# hh.net
KiCad netlist of a schematic drawn in EAGLE
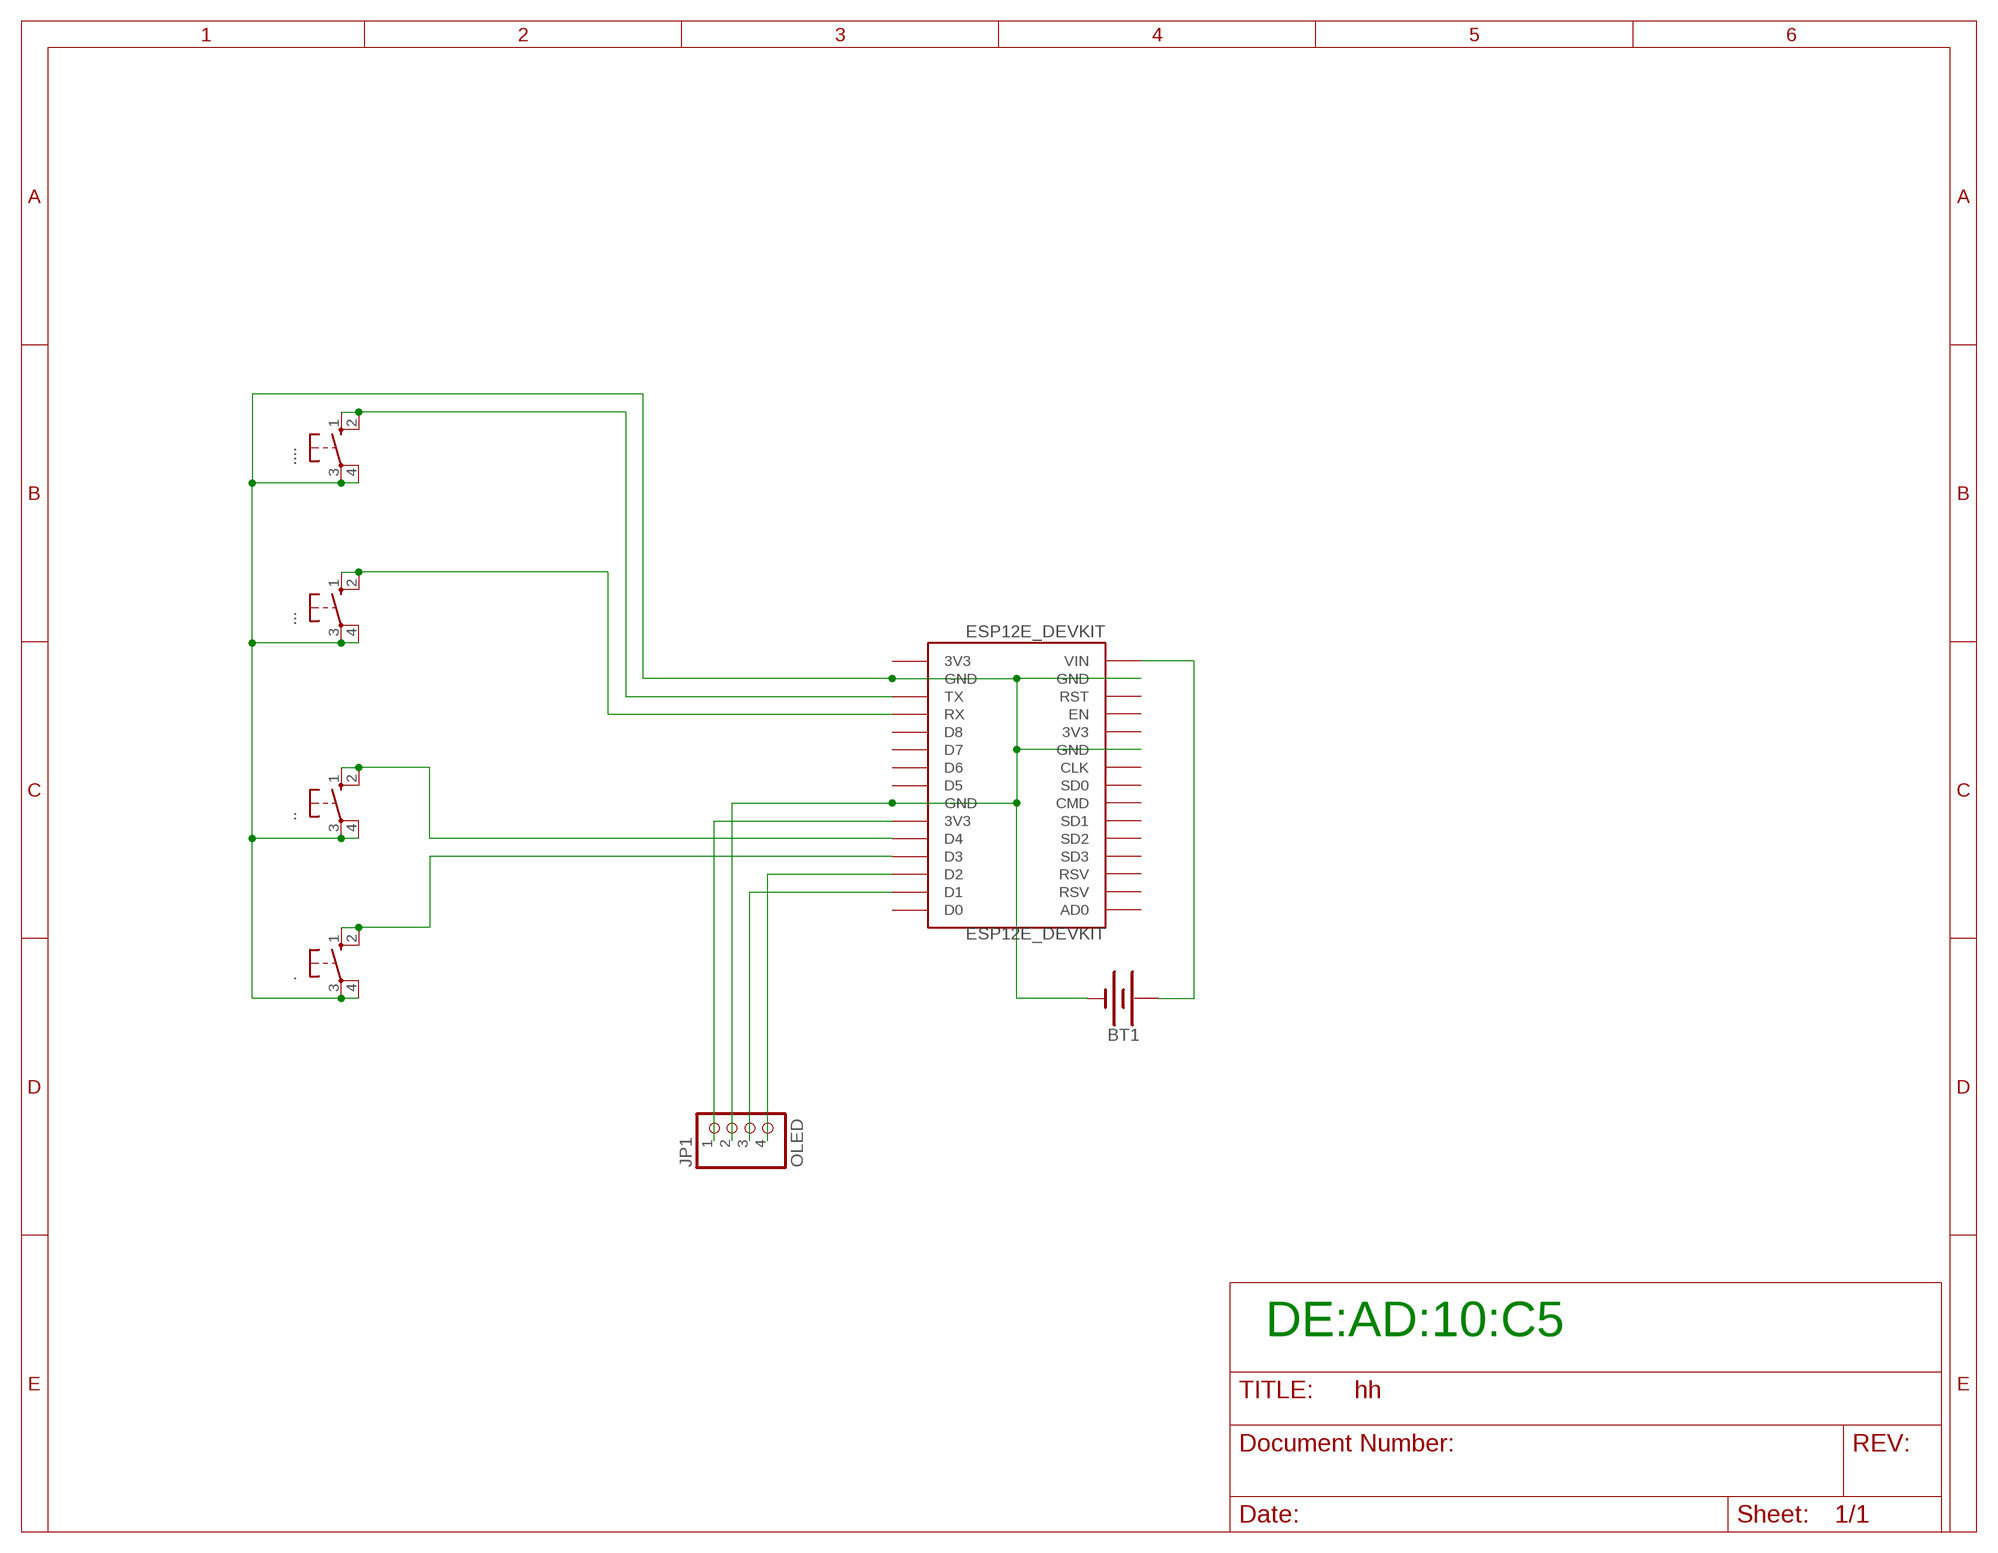
[diagram p0: schematic, sheet 1]

(export (version "E")
  (design (tool "Eeschema 10.0.6"))
  (components
    (comp (ref ".")
      (value "10-XX")
      (footprint "eagle-import:B3F-10XX")
      (fields (field (name "MPN") "B3F-1000"))
      (libsource (lib "eagle-import") (part "10-XX"))
    )
    (comp (ref "..")
      (value "10-XX")
      (footprint "eagle-import:B3F-10XX")
      (fields (field (name "MPN") "B3F-1000"))
      (libsource (lib "eagle-import") (part "10-XX"))
    )
    (comp (ref "...")
      (value "10-XX")
      (footprint "eagle-import:B3F-10XX")
      (fields (field (name "MPN") "B3F-1000"))
      (libsource (lib "eagle-import") (part "10-XX"))
    )
    (comp (ref "....")
      (value "10-XX")
      (footprint "eagle-import:B3F-10XX")
      (fields (field (name "MPN") "B3F-1000"))
      (libsource (lib "eagle-import") (part "10-XX"))
    )
    (comp (ref "BT1")
      (value "BATTERY-18650")
      (footprint "eagle-import:BATTERY_18650-HOLDER")
      (libsource (lib "eagle-import") (part "BATTERY-18650"))
    )
    (comp (ref "ESP12E_DEVKIT")
      (value "ESP12E_DEVKIT")
      (footprint "eagle-import:ESP12E_DEVKIT")
      (libsource (lib "eagle-import") (part "ESP12E_DEVKIT"))
    )
    (comp (ref "JP1")
      (value "OLED")
      (footprint "eagle-import:1X04")
      (libsource (lib "eagle-import") (part "PINHD-1X4"))
    )
  )
  (nets
    (net (code "1") (name "Net-(.-P)") (class "Default")
      (node (ref ".") (pin "3") (pinfunction "P_3") (pintype "passive"))
      (node (ref ".") (pin "4") (pinfunction "P1_4") (pintype "passive"))
      (node (ref "..") (pin "3") (pinfunction "P_3") (pintype "passive"))
      (node (ref "..") (pin "4") (pinfunction "P1_4") (pintype "passive"))
      (node (ref "...") (pin "3") (pinfunction "P_3") (pintype "passive"))
      (node (ref "...") (pin "4") (pinfunction "P1_4") (pintype "passive"))
      (node (ref "....") (pin "3") (pinfunction "P_3") (pintype "passive"))
      (node (ref "....") (pin "4") (pinfunction "P1_4") (pintype "passive"))
      (node (ref "BT1") (pin "GND@1") (pinfunction "-_GND@1") (pintype "power_in"))
      (node (ref "ESP12E_DEVKIT") (pin "GND@0") (pinfunction "GND_GND@0") (pintype "bidirectional"))
      (node (ref "ESP12E_DEVKIT") (pin "GND@1") (pinfunction "GND_GND@1") (pintype "bidirectional"))
      (node (ref "ESP12E_DEVKIT") (pin "GND@2") (pinfunction "GND_GND@2") (pintype "bidirectional"))
      (node (ref "ESP12E_DEVKIT") (pin "GND@3") (pinfunction "GND_GND@3") (pintype "bidirectional"))
      (node (ref "JP1") (pin "2") (pinfunction "2_2") (pintype "passive"))
    )
    (net (code "2") (name "Net-(.-S)") (class "Default")
      (node (ref ".") (pin "1") (pinfunction "S_1") (pintype "passive"))
      (node (ref ".") (pin "2") (pinfunction "S1_2") (pintype "passive"))
      (node (ref "ESP12E_DEVKIT") (pin "D3") (pinfunction "D3_D3") (pintype "bidirectional"))
    )
    (net (code "3") (name "Net-(..-S)") (class "Default")
      (node (ref "..") (pin "1") (pinfunction "S_1") (pintype "passive"))
      (node (ref "..") (pin "2") (pinfunction "S1_2") (pintype "passive"))
      (node (ref "ESP12E_DEVKIT") (pin "D4") (pinfunction "D4_D4") (pintype "bidirectional"))
    )
    (net (code "4") (name "Net-(...-S)") (class "Default")
      (node (ref "...") (pin "1") (pinfunction "S_1") (pintype "passive"))
      (node (ref "...") (pin "2") (pinfunction "S1_2") (pintype "passive"))
      (node (ref "ESP12E_DEVKIT") (pin "RX") (pinfunction "RX_RX") (pintype "bidirectional"))
    )
    (net (code "5") (name "Net-(....-S)") (class "Default")
      (node (ref "....") (pin "1") (pinfunction "S_1") (pintype "passive"))
      (node (ref "....") (pin "2") (pinfunction "S1_2") (pintype "passive"))
      (node (ref "ESP12E_DEVKIT") (pin "TX") (pinfunction "TX_TX") (pintype "bidirectional"))
    )
    (net (code "6") (name "Net-(BT1-+)") (class "Default")
      (node (ref "BT1") (pin "PWR@1") (pinfunction "+_PWR@1") (pintype "power_in"))
      (node (ref "ESP12E_DEVKIT") (pin "VIN") (pinfunction "VIN_VIN") (pintype "bidirectional"))
    )
    (net (code "7") (name "Net-(ESP12E_DEVKIT-3V3-Pad3V3@1)") (class "Default")
      (node (ref "ESP12E_DEVKIT") (pin "3V3@1") (pinfunction "3V3_3V3@1") (pintype "bidirectional"))
      (node (ref "JP1") (pin "1") (pinfunction "1_1") (pintype "passive"))
    )
    (net (code "8") (name "Net-(ESP12E_DEVKIT-PadD1)") (class "Default")
      (node (ref "ESP12E_DEVKIT") (pin "D1") (pinfunction "D1_D1") (pintype "bidirectional"))
      (node (ref "JP1") (pin "3") (pinfunction "3_3") (pintype "passive"))
    )
    (net (code "9") (name "Net-(ESP12E_DEVKIT-PadD2)") (class "Default")
      (node (ref "ESP12E_DEVKIT") (pin "D2") (pinfunction "D2_D2") (pintype "bidirectional"))
      (node (ref "JP1") (pin "4") (pinfunction "4_4") (pintype "passive"))
    )
    (net (code "10") (name "unconnected-(ESP12E_DEVKIT-3V3-Pad3V3@0)") (class "Default")
      (node (ref "ESP12E_DEVKIT") (pin "3V3@0") (pinfunction "3V3_3V3@0") (pintype "bidirectional"))
    )
    (net (code "11") (name "unconnected-(ESP12E_DEVKIT-3V3-Pad3V3@2)") (class "Default")
      (node (ref "ESP12E_DEVKIT") (pin "3V3@2") (pinfunction "3V3_3V3@2") (pintype "bidirectional"))
    )
    (net (code "12") (name "unconnected-(ESP12E_DEVKIT-PadAD0)") (class "Default")
      (node (ref "ESP12E_DEVKIT") (pin "AD0") (pinfunction "AD0_AD0") (pintype "bidirectional"))
    )
    (net (code "13") (name "unconnected-(ESP12E_DEVKIT-PadCLK)") (class "Default")
      (node (ref "ESP12E_DEVKIT") (pin "CLK") (pinfunction "CLK_CLK") (pintype "bidirectional"))
    )
    (net (code "14") (name "unconnected-(ESP12E_DEVKIT-PadCMD)") (class "Default")
      (node (ref "ESP12E_DEVKIT") (pin "CMD") (pinfunction "CMD_CMD") (pintype "bidirectional"))
    )
    (net (code "15") (name "unconnected-(ESP12E_DEVKIT-PadD0)") (class "Default")
      (node (ref "ESP12E_DEVKIT") (pin "D0") (pinfunction "D0_D0") (pintype "bidirectional"))
    )
    (net (code "16") (name "unconnected-(ESP12E_DEVKIT-PadD5)") (class "Default")
      (node (ref "ESP12E_DEVKIT") (pin "D5") (pinfunction "D5_D5") (pintype "bidirectional"))
    )
    (net (code "17") (name "unconnected-(ESP12E_DEVKIT-PadD6)") (class "Default")
      (node (ref "ESP12E_DEVKIT") (pin "D6") (pinfunction "D6_D6") (pintype "bidirectional"))
    )
    (net (code "18") (name "unconnected-(ESP12E_DEVKIT-PadD7)") (class "Default")
      (node (ref "ESP12E_DEVKIT") (pin "D7") (pinfunction "D7_D7") (pintype "bidirectional"))
    )
    (net (code "19") (name "unconnected-(ESP12E_DEVKIT-PadD8)") (class "Default")
      (node (ref "ESP12E_DEVKIT") (pin "D8") (pinfunction "D8_D8") (pintype "bidirectional"))
    )
    (net (code "20") (name "unconnected-(ESP12E_DEVKIT-PadEN)") (class "Default")
      (node (ref "ESP12E_DEVKIT") (pin "EN") (pinfunction "EN_EN") (pintype "bidirectional"))
    )
    (net (code "21") (name "unconnected-(ESP12E_DEVKIT-PadRST)") (class "Default")
      (node (ref "ESP12E_DEVKIT") (pin "RST") (pinfunction "RST_RST") (pintype "bidirectional"))
    )
    (net (code "22") (name "unconnected-(ESP12E_DEVKIT-PadSD0)") (class "Default")
      (node (ref "ESP12E_DEVKIT") (pin "SD0") (pinfunction "SD0_SD0") (pintype "bidirectional"))
    )
    (net (code "23") (name "unconnected-(ESP12E_DEVKIT-PadSD1)") (class "Default")
      (node (ref "ESP12E_DEVKIT") (pin "SD1") (pinfunction "SD1_SD1") (pintype "bidirectional"))
    )
    (net (code "24") (name "unconnected-(ESP12E_DEVKIT-PadSD2)") (class "Default")
      (node (ref "ESP12E_DEVKIT") (pin "SD2") (pinfunction "SD2_SD2") (pintype "bidirectional"))
    )
    (net (code "25") (name "unconnected-(ESP12E_DEVKIT-PadSD3)") (class "Default")
      (node (ref "ESP12E_DEVKIT") (pin "SD3") (pinfunction "SD3_SD3") (pintype "bidirectional"))
    )
    (net (code "26") (name "unconnected-(ESP12E_DEVKIT-RSV-PadRSV@0)") (class "Default")
      (node (ref "ESP12E_DEVKIT") (pin "RSV@0") (pinfunction "RSV_RSV@0") (pintype "bidirectional"))
    )
    (net (code "27") (name "unconnected-(ESP12E_DEVKIT-RSV-PadRSV@1)") (class "Default")
      (node (ref "ESP12E_DEVKIT") (pin "RSV@1") (pinfunction "RSV_RSV@1") (pintype "bidirectional"))
    )
  )
)
